# DIY_V2.net
KiCad netlist of a schematic drawn in Altium Designer
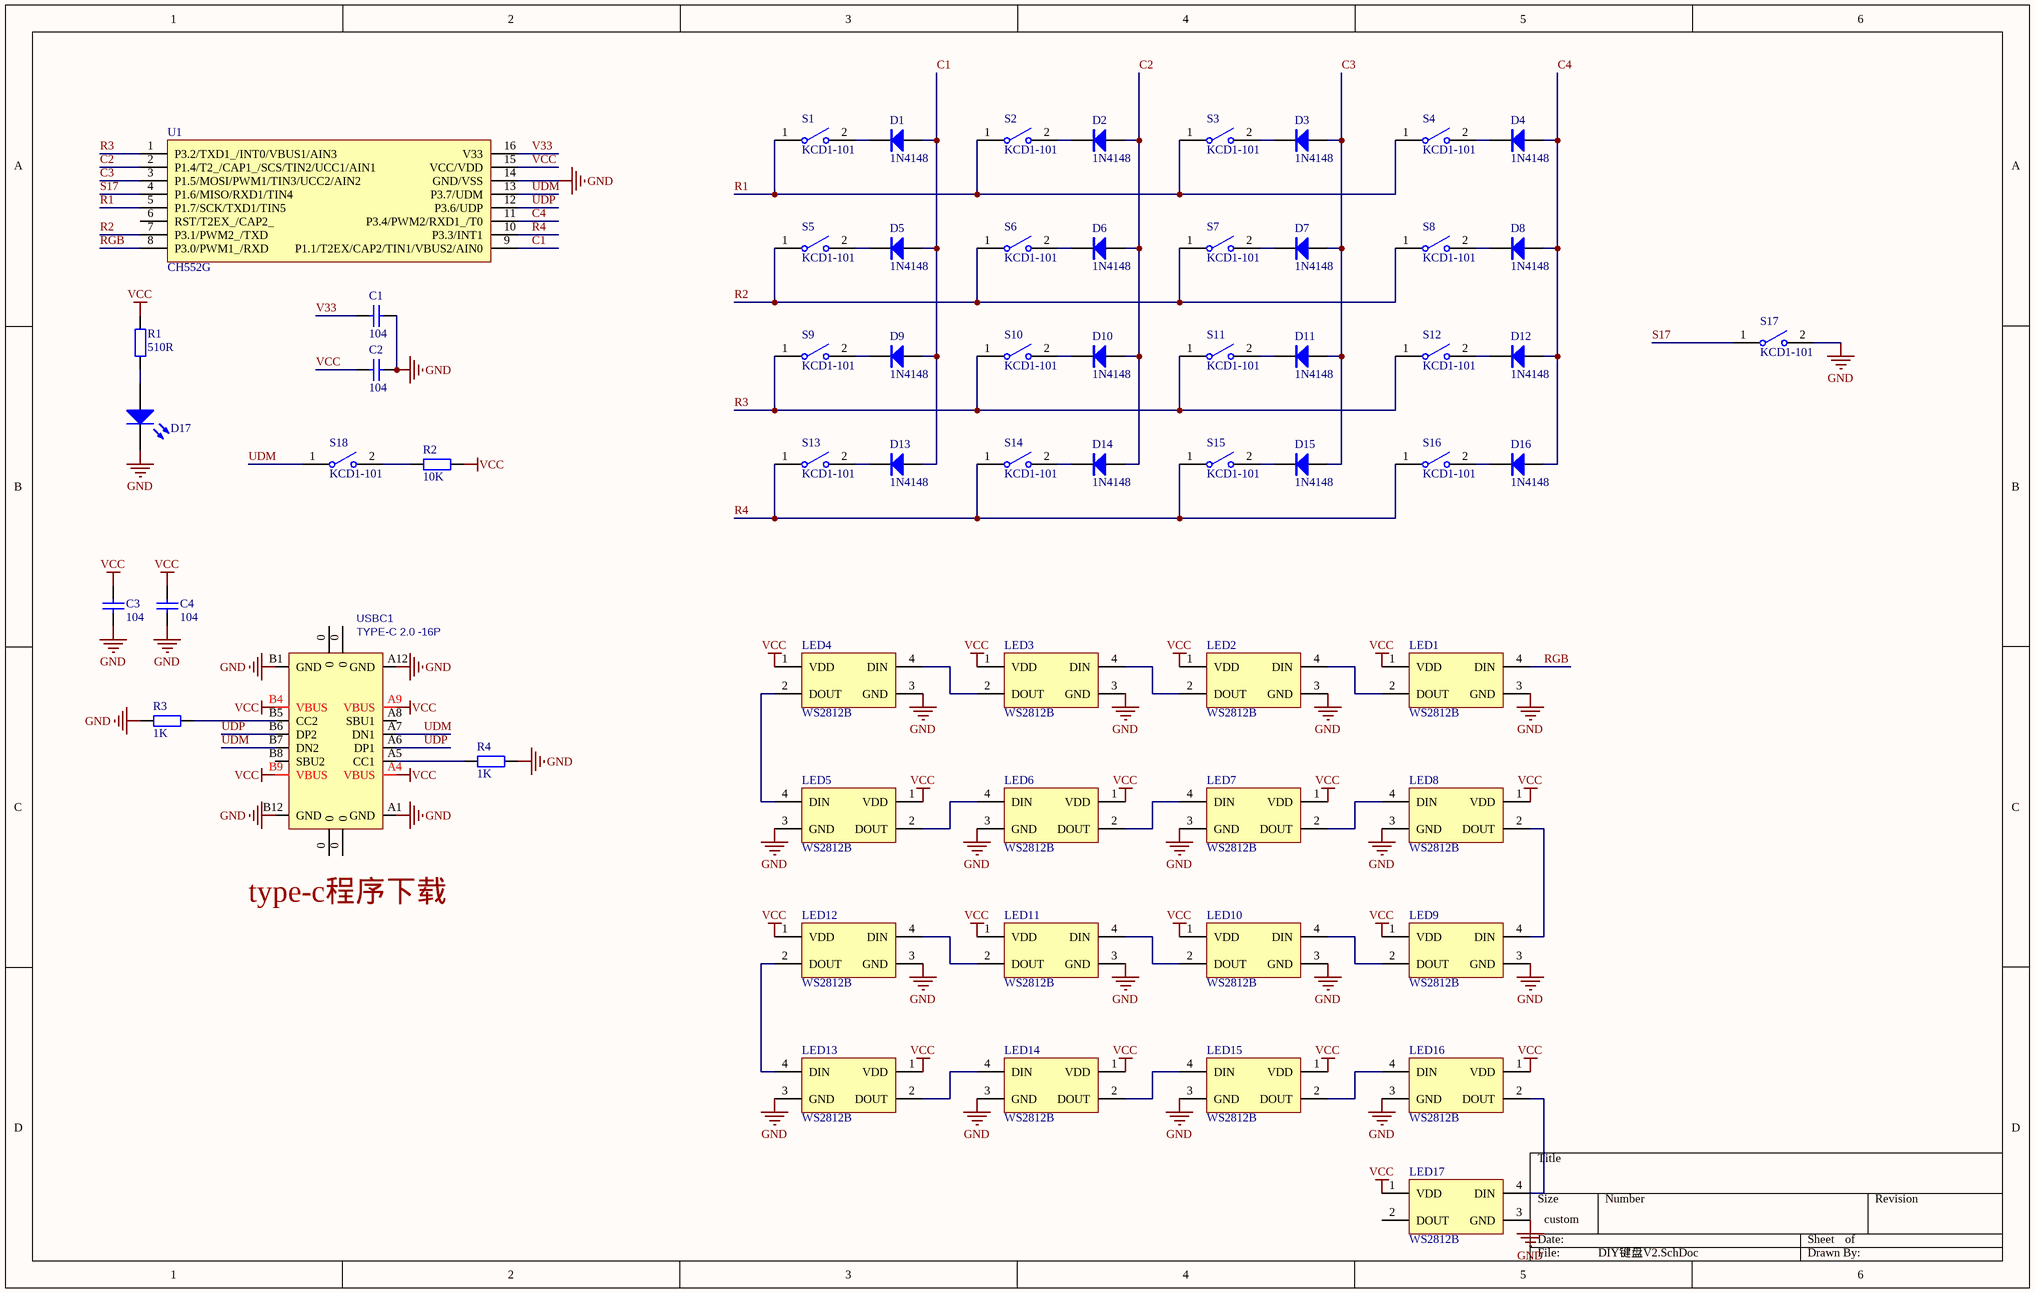
[diagram p0: DIY键盘V2.SchDoc]

(export (version "E")
  (design (tool "Eeschema 10.0.6"))
  (components
    (comp (ref "C1")
      (value "104")
      (footprint "C0603_M")
      (description "贴片电容/MLCC电容")
      (libsource (lib "0.1 - 电阻-电容-电感-晶振-晶体-磁珠-电位器-法拉电容-馈通电容") (part "C"))
    )
    (comp (ref "C2")
      (value "104")
      (footprint "C0603_M")
      (description "贴片电容/MLCC电容")
      (libsource (lib "0.1 - 电阻-电容-电感-晶振-晶体-磁珠-电位器-法拉电容-馈通电容") (part "C"))
    )
    (comp (ref "C3")
      (value "104")
      (footprint "C0603_M")
      (description "贴片电容/MLCC电容")
      (libsource (lib "0.1 - 电阻-电容-电感-晶振-晶体-磁珠-电位器-法拉电容-馈通电容") (part "C"))
    )
    (comp (ref "C4")
      (value "104")
      (footprint "C0603_M")
      (description "贴片电容/MLCC电容")
      (libsource (lib "0.1 - 电阻-电容-电感-晶振-晶体-磁珠-电位器-法拉电容-馈通电容") (part "C"))
    )
    (comp (ref "D1")
      (value "1N4148")
      (footprint "SOD-323")
      (description "开关二极管")
      (libsource (lib "0.2 - 二极管-TVS-ESD-整流桥-放电管") (part "1N4148"))
    )
    (comp (ref "D2")
      (value "1N4148")
      (footprint "SOD-323")
      (description "开关二极管")
      (libsource (lib "0.2 - 二极管-TVS-ESD-整流桥-放电管") (part "1N4148"))
    )
    (comp (ref "D3")
      (value "1N4148")
      (footprint "SOD-323")
      (description "开关二极管")
      (libsource (lib "0.2 - 二极管-TVS-ESD-整流桥-放电管") (part "1N4148"))
    )
    (comp (ref "D4")
      (value "1N4148")
      (footprint "SOD-323")
      (description "开关二极管")
      (libsource (lib "0.2 - 二极管-TVS-ESD-整流桥-放电管") (part "1N4148"))
    )
    (comp (ref "D5")
      (value "1N4148")
      (footprint "SOD-323")
      (description "开关二极管")
      (libsource (lib "0.2 - 二极管-TVS-ESD-整流桥-放电管") (part "1N4148"))
    )
    (comp (ref "D6")
      (value "1N4148")
      (footprint "SOD-323")
      (description "开关二极管")
      (libsource (lib "0.2 - 二极管-TVS-ESD-整流桥-放电管") (part "1N4148"))
    )
    (comp (ref "D7")
      (value "1N4148")
      (footprint "SOD-323")
      (description "开关二极管")
      (libsource (lib "0.2 - 二极管-TVS-ESD-整流桥-放电管") (part "1N4148"))
    )
    (comp (ref "D8")
      (value "1N4148")
      (footprint "SOD-323")
      (description "开关二极管")
      (libsource (lib "0.2 - 二极管-TVS-ESD-整流桥-放电管") (part "1N4148"))
    )
    (comp (ref "D9")
      (value "1N4148")
      (footprint "SOD-323")
      (description "开关二极管")
      (libsource (lib "0.2 - 二极管-TVS-ESD-整流桥-放电管") (part "1N4148"))
    )
    (comp (ref "D10")
      (value "1N4148")
      (footprint "SOD-323")
      (description "开关二极管")
      (libsource (lib "0.2 - 二极管-TVS-ESD-整流桥-放电管") (part "1N4148"))
    )
    (comp (ref "D11")
      (value "1N4148")
      (footprint "SOD-323")
      (description "开关二极管")
      (libsource (lib "0.2 - 二极管-TVS-ESD-整流桥-放电管") (part "1N4148"))
    )
    (comp (ref "D12")
      (value "1N4148")
      (footprint "SOD-323")
      (description "开关二极管")
      (libsource (lib "0.2 - 二极管-TVS-ESD-整流桥-放电管") (part "1N4148"))
    )
    (comp (ref "D13")
      (value "1N4148")
      (footprint "SOD-323")
      (description "开关二极管")
      (libsource (lib "0.2 - 二极管-TVS-ESD-整流桥-放电管") (part "1N4148"))
    )
    (comp (ref "D14")
      (value "1N4148")
      (footprint "SOD-323")
      (description "开关二极管")
      (libsource (lib "0.2 - 二极管-TVS-ESD-整流桥-放电管") (part "1N4148"))
    )
    (comp (ref "D15")
      (value "1N4148")
      (footprint "SOD-323")
      (description "开关二极管")
      (libsource (lib "0.2 - 二极管-TVS-ESD-整流桥-放电管") (part "1N4148"))
    )
    (comp (ref "D16")
      (value "1N4148")
      (footprint "SOD-323")
      (description "开关二极管")
      (libsource (lib "0.2 - 二极管-TVS-ESD-整流桥-放电管") (part "1N4148"))
    )
    (comp (ref "D17")
      (value "LED")
      (footprint "LED0603_B")
      (description "发光二极管")
      (libsource (lib "0.3 - LED发光二极管-IR二极管_接收管-光耦") (part "LED"))
    )
    (comp (ref "LED1")
      (value "WS2812B")
      (footprint "LED-SMD_L3.2-W2.8-BR_DY-S352818")
      (description "WS2812B反贴")
      (libsource (lib "0.3 - LED发光二极管-IR二极管_接收管-光耦") (part "WS2812B"))
    )
    (comp (ref "LED2")
      (value "WS2812B")
      (footprint "LED-SMD_L3.2-W2.8-BR_DY-S352818")
      (description "WS2812B反贴")
      (libsource (lib "0.3 - LED发光二极管-IR二极管_接收管-光耦") (part "WS2812B"))
    )
    (comp (ref "LED3")
      (value "WS2812B")
      (footprint "LED-SMD_L3.2-W2.8-BR_DY-S352818")
      (description "WS2812B反贴")
      (libsource (lib "0.3 - LED发光二极管-IR二极管_接收管-光耦") (part "WS2812B"))
    )
    (comp (ref "LED4")
      (value "WS2812B")
      (footprint "LED-SMD_L3.2-W2.8-BR_DY-S352818")
      (description "WS2812B反贴")
      (libsource (lib "0.3 - LED发光二极管-IR二极管_接收管-光耦") (part "WS2812B"))
    )
    (comp (ref "LED5")
      (value "WS2812B")
      (footprint "LED-SMD_L3.2-W2.8-BR_DY-S352818")
      (description "WS2812B反贴")
      (libsource (lib "") (part "WS2812B_1"))
    )
    (comp (ref "LED6")
      (value "WS2812B")
      (footprint "LED-SMD_L3.2-W2.8-BR_DY-S352818")
      (description "WS2812B反贴")
      (libsource (lib "") (part "WS2812B_1"))
    )
    (comp (ref "LED7")
      (value "WS2812B")
      (footprint "LED-SMD_L3.2-W2.8-BR_DY-S352818")
      (description "WS2812B反贴")
      (libsource (lib "") (part "WS2812B_1"))
    )
    (comp (ref "LED8")
      (value "WS2812B")
      (footprint "LED-SMD_L3.2-W2.8-BR_DY-S352818")
      (description "WS2812B反贴")
      (libsource (lib "") (part "WS2812B_1"))
    )
    (comp (ref "LED9")
      (value "WS2812B")
      (footprint "LED-SMD_L3.2-W2.8-BR_DY-S352818")
      (description "WS2812B反贴")
      (libsource (lib "0.3 - LED发光二极管-IR二极管_接收管-光耦") (part "WS2812B"))
    )
    (comp (ref "LED10")
      (value "WS2812B")
      (footprint "LED-SMD_L3.2-W2.8-BR_DY-S352818")
      (description "WS2812B反贴")
      (libsource (lib "0.3 - LED发光二极管-IR二极管_接收管-光耦") (part "WS2812B"))
    )
    (comp (ref "LED11")
      (value "WS2812B")
      (footprint "LED-SMD_L3.2-W2.8-BR_DY-S352818")
      (description "WS2812B反贴")
      (libsource (lib "0.3 - LED发光二极管-IR二极管_接收管-光耦") (part "WS2812B"))
    )
    (comp (ref "LED12")
      (value "WS2812B")
      (footprint "LED-SMD_L3.2-W2.8-BR_DY-S352818")
      (description "WS2812B反贴")
      (libsource (lib "0.3 - LED发光二极管-IR二极管_接收管-光耦") (part "WS2812B"))
    )
    (comp (ref "LED13")
      (value "WS2812B")
      (footprint "LED-SMD_L3.2-W2.8-BR_DY-S352818")
      (description "WS2812B反贴")
      (libsource (lib "") (part "WS2812B_1"))
    )
    (comp (ref "LED14")
      (value "WS2812B")
      (footprint "LED-SMD_L3.2-W2.8-BR_DY-S352818")
      (description "WS2812B反贴")
      (libsource (lib "") (part "WS2812B_1"))
    )
    (comp (ref "LED15")
      (value "WS2812B")
      (footprint "LED-SMD_L3.2-W2.8-BR_DY-S352818")
      (description "WS2812B反贴")
      (libsource (lib "") (part "WS2812B_1"))
    )
    (comp (ref "LED16")
      (value "WS2812B")
      (footprint "LED-SMD_L3.2-W2.8-BR_DY-S352818")
      (description "WS2812B反贴")
      (libsource (lib "") (part "WS2812B_1"))
    )
    (comp (ref "LED17")
      (value "WS2812B")
      (footprint "LED-SMD_L3.2-W2.8-BR_DY-S352818")
      (description "WS2812B反贴")
      (libsource (lib "0.3 - LED发光二极管-IR二极管_接收管-光耦") (part "WS2812B"))
    )
    (comp (ref "R1")
      (value "510R")
      (footprint "R0603_M")
      (description "贴片电阻")
      (libsource (lib "0.1 - 电阻-电容-电感-晶振-晶体-磁珠-电位器-法拉电容-馈通电容") (part "R"))
    )
    (comp (ref "R2")
      (value "10K")
      (footprint "R0603_M")
      (description "贴片电阻")
      (libsource (lib "0.1 - 电阻-电容-电感-晶振-晶体-磁珠-电位器-法拉电容-馈通电容") (part "R"))
    )
    (comp (ref "R3")
      (value "1K")
      (footprint "R0603_M")
      (description "贴片电阻")
      (libsource (lib "0.1 - 电阻-电容-电感-晶振-晶体-磁珠-电位器-法拉电容-馈通电容") (part "R"))
    )
    (comp (ref "R4")
      (value "1K")
      (footprint "R0603_M")
      (description "贴片电阻")
      (libsource (lib "0.1 - 电阻-电容-电感-晶振-晶体-磁珠-电位器-法拉电容-馈通电容") (part "R"))
    )
    (comp (ref "S1")
      (value "KCD1-101")
      (footprint "DIY键盘:KEY-TH_CPG1511F01S0X")
      (description "1路单刀船型开关")
      (libsource (lib "0.5 - 按键-开关-蜂鸣器-保险丝-电池-测试点-Mark点-铜柱") (part "KCD1-101"))
    )
    (comp (ref "S2")
      (value "KCD1-101")
      (footprint "DIY键盘:KEY-TH_CPG1511F01S0X")
      (description "1路单刀船型开关")
      (libsource (lib "0.5 - 按键-开关-蜂鸣器-保险丝-电池-测试点-Mark点-铜柱") (part "KCD1-101"))
    )
    (comp (ref "S3")
      (value "KCD1-101")
      (footprint "DIY键盘:KEY-TH_CPG1511F01S0X")
      (description "1路单刀船型开关")
      (libsource (lib "0.5 - 按键-开关-蜂鸣器-保险丝-电池-测试点-Mark点-铜柱") (part "KCD1-101"))
    )
    (comp (ref "S4")
      (value "KCD1-101")
      (footprint "DIY键盘:KEY-TH_CPG1511F01S0X")
      (description "1路单刀船型开关")
      (libsource (lib "0.5 - 按键-开关-蜂鸣器-保险丝-电池-测试点-Mark点-铜柱") (part "KCD1-101"))
    )
    (comp (ref "S5")
      (value "KCD1-101")
      (footprint "DIY键盘:KEY-TH_CPG1511F01S0X")
      (description "1路单刀船型开关")
      (libsource (lib "0.5 - 按键-开关-蜂鸣器-保险丝-电池-测试点-Mark点-铜柱") (part "KCD1-101"))
    )
    (comp (ref "S6")
      (value "KCD1-101")
      (footprint "DIY键盘:KEY-TH_CPG1511F01S0X")
      (description "1路单刀船型开关")
      (libsource (lib "0.5 - 按键-开关-蜂鸣器-保险丝-电池-测试点-Mark点-铜柱") (part "KCD1-101"))
    )
    (comp (ref "S7")
      (value "KCD1-101")
      (footprint "DIY键盘:KEY-TH_CPG1511F01S0X")
      (description "1路单刀船型开关")
      (libsource (lib "0.5 - 按键-开关-蜂鸣器-保险丝-电池-测试点-Mark点-铜柱") (part "KCD1-101"))
    )
    (comp (ref "S8")
      (value "KCD1-101")
      (footprint "DIY键盘:KEY-TH_CPG1511F01S0X")
      (description "1路单刀船型开关")
      (libsource (lib "0.5 - 按键-开关-蜂鸣器-保险丝-电池-测试点-Mark点-铜柱") (part "KCD1-101"))
    )
    (comp (ref "S9")
      (value "KCD1-101")
      (footprint "DIY键盘:KEY-TH_CPG1511F01S0X")
      (description "1路单刀船型开关")
      (libsource (lib "0.5 - 按键-开关-蜂鸣器-保险丝-电池-测试点-Mark点-铜柱") (part "KCD1-101"))
    )
    (comp (ref "S10")
      (value "KCD1-101")
      (footprint "DIY键盘:KEY-TH_CPG1511F01S0X")
      (description "1路单刀船型开关")
      (libsource (lib "0.5 - 按键-开关-蜂鸣器-保险丝-电池-测试点-Mark点-铜柱") (part "KCD1-101"))
    )
    (comp (ref "S11")
      (value "KCD1-101")
      (footprint "DIY键盘:KEY-TH_CPG1511F01S0X")
      (description "1路单刀船型开关")
      (libsource (lib "0.5 - 按键-开关-蜂鸣器-保险丝-电池-测试点-Mark点-铜柱") (part "KCD1-101"))
    )
    (comp (ref "S12")
      (value "KCD1-101")
      (footprint "DIY键盘:KEY-TH_CPG1511F01S0X")
      (description "1路单刀船型开关")
      (libsource (lib "0.5 - 按键-开关-蜂鸣器-保险丝-电池-测试点-Mark点-铜柱") (part "KCD1-101"))
    )
    (comp (ref "S13")
      (value "KCD1-101")
      (footprint "DIY键盘:KEY-TH_CPG1511F01S0X")
      (description "1路单刀船型开关")
      (libsource (lib "0.5 - 按键-开关-蜂鸣器-保险丝-电池-测试点-Mark点-铜柱") (part "KCD1-101"))
    )
    (comp (ref "S14")
      (value "KCD1-101")
      (footprint "DIY键盘:KEY-TH_CPG1511F01S0X")
      (description "1路单刀船型开关")
      (libsource (lib "0.5 - 按键-开关-蜂鸣器-保险丝-电池-测试点-Mark点-铜柱") (part "KCD1-101"))
    )
    (comp (ref "S15")
      (value "KCD1-101")
      (footprint "DIY键盘:KEY-TH_CPG1511F01S0X")
      (description "1路单刀船型开关")
      (libsource (lib "0.5 - 按键-开关-蜂鸣器-保险丝-电池-测试点-Mark点-铜柱") (part "KCD1-101"))
    )
    (comp (ref "S16")
      (value "KCD1-101")
      (footprint "DIY键盘:KEY-TH_CPG1511F01S0X")
      (description "1路单刀船型开关")
      (libsource (lib "0.5 - 按键-开关-蜂鸣器-保险丝-电池-测试点-Mark点-铜柱") (part "KCD1-101"))
    )
    (comp (ref "S17")
      (value "KCD1-101")
      (footprint "DIY键盘:KEY-TH_CPG1511F01S0X")
      (description "1路单刀船型开关")
      (libsource (lib "0.5 - 按键-开关-蜂鸣器-保险丝-电池-测试点-Mark点-铜柱") (part "KCD1-101"))
    )
    (comp (ref "S18")
      (value "KCD1-101")
      (footprint "SW SMD-3*6*2.5")
      (description "1路单刀船型开关")
      (libsource (lib "0.5 - 按键-开关-蜂鸣器-保险丝-电池-测试点-Mark点-铜柱") (part "KCD1-101"))
    )
    (comp (ref "U1")
      (value "CH552G")
      (footprint "DIY键盘:SOP-16_L10.0-W3.9-P1.27-LS6.0-BL")
      (description "8 DIgits")
      (libsource (lib "1.8 - CH340系列编程器芯片") (part "CH552G"))
    )
    (comp (ref "USBC1")
      (value "TYPE-C 2.0 -16P")
      (footprint "USB-C-SMD_16P")
      (description "USB2.0_Type-C_16Pin母座")
      (libsource (lib "0.6 - 电源-以太网-音频-Type-C USB插座") (part "USB2.0_Type-C_16Pin"))
    )
  )
  (nets
    (net (code "1") (name "/C1") (class "Default")
      (node (ref "D1") (pin "1") (pinfunction "A_1") (pintype "passive"))
      (node (ref "D13") (pin "1") (pinfunction "A_1") (pintype "passive"))
      (node (ref "D5") (pin "1") (pinfunction "A_1") (pintype "passive"))
      (node (ref "D9") (pin "1") (pinfunction "A_1") (pintype "passive"))
      (node (ref "U1") (pin "9") (pinfunction "P1.1/T2EX/CAP2/TIN1/VBUS2/AIN0_9") (pintype "passive"))
    )
    (net (code "2") (name "/C2") (class "Default")
      (node (ref "D10") (pin "1") (pinfunction "A_1") (pintype "passive"))
      (node (ref "D14") (pin "1") (pinfunction "A_1") (pintype "passive"))
      (node (ref "D2") (pin "1") (pinfunction "A_1") (pintype "passive"))
      (node (ref "D6") (pin "1") (pinfunction "A_1") (pintype "passive"))
      (node (ref "U1") (pin "2") (pinfunction "P1.4/T2_/CAP1_/SCS/TIN2/UCC1/AIN1_2") (pintype "passive"))
    )
    (net (code "3") (name "/C3") (class "Default")
      (node (ref "D11") (pin "1") (pinfunction "A_1") (pintype "passive"))
      (node (ref "D15") (pin "1") (pinfunction "A_1") (pintype "passive"))
      (node (ref "D3") (pin "1") (pinfunction "A_1") (pintype "passive"))
      (node (ref "D7") (pin "1") (pinfunction "A_1") (pintype "passive"))
      (node (ref "U1") (pin "3") (pinfunction "P1.5/MOSI/PWM1/TIN3/UCC2/AIN2_3") (pintype "passive"))
    )
    (net (code "4") (name "/C4") (class "Default")
      (node (ref "D12") (pin "1") (pinfunction "A_1") (pintype "passive"))
      (node (ref "D16") (pin "1") (pinfunction "A_1") (pintype "passive"))
      (node (ref "D4") (pin "1") (pinfunction "A_1") (pintype "passive"))
      (node (ref "D8") (pin "1") (pinfunction "A_1") (pintype "passive"))
      (node (ref "U1") (pin "11") (pinfunction "P3.4/PWM2/RXD1_/T0_11") (pintype "passive"))
    )
    (net (code "5") (name "/R1") (class "Default")
      (node (ref "S1") (pin "1") (pinfunction "1_1") (pintype "passive"))
      (node (ref "S2") (pin "1") (pinfunction "1_1") (pintype "passive"))
      (node (ref "S3") (pin "1") (pinfunction "1_1") (pintype "passive"))
      (node (ref "S4") (pin "1") (pinfunction "1_1") (pintype "passive"))
      (node (ref "U1") (pin "5") (pinfunction "P1.7/SCK/TXD1/TIN5_5") (pintype "passive"))
    )
    (net (code "6") (name "/R2") (class "Default")
      (node (ref "S5") (pin "1") (pinfunction "1_1") (pintype "passive"))
      (node (ref "S6") (pin "1") (pinfunction "1_1") (pintype "passive"))
      (node (ref "S7") (pin "1") (pinfunction "1_1") (pintype "passive"))
      (node (ref "S8") (pin "1") (pinfunction "1_1") (pintype "passive"))
      (node (ref "U1") (pin "7") (pinfunction "P3.1/PWM2_/TXD_7") (pintype "passive"))
    )
    (net (code "7") (name "/R3") (class "Default")
      (node (ref "S10") (pin "1") (pinfunction "1_1") (pintype "passive"))
      (node (ref "S11") (pin "1") (pinfunction "1_1") (pintype "passive"))
      (node (ref "S12") (pin "1") (pinfunction "1_1") (pintype "passive"))
      (node (ref "S9") (pin "1") (pinfunction "1_1") (pintype "passive"))
      (node (ref "U1") (pin "1") (pinfunction "P3.2/TXD1_/INT0/VBUS1/AIN3_1") (pintype "passive"))
    )
    (net (code "8") (name "/R4") (class "Default")
      (node (ref "S13") (pin "1") (pinfunction "1_1") (pintype "passive"))
      (node (ref "S14") (pin "1") (pinfunction "1_1") (pintype "passive"))
      (node (ref "S15") (pin "1") (pinfunction "1_1") (pintype "passive"))
      (node (ref "S16") (pin "1") (pinfunction "1_1") (pintype "passive"))
      (node (ref "U1") (pin "10") (pinfunction "P3.3/INT1_10") (pintype "passive"))
    )
    (net (code "9") (name "/RGB") (class "Default")
      (node (ref "LED1") (pin "4") (pinfunction "DIN_4") (pintype "passive"))
      (node (ref "U1") (pin "8") (pinfunction "P3.0/PWM1_/RXD_8") (pintype "passive"))
    )
    (net (code "10") (name "/S17") (class "Default")
      (node (ref "S17") (pin "1") (pinfunction "1_1") (pintype "passive"))
      (node (ref "U1") (pin "4") (pinfunction "P1.6/MISO/RXD1/TIN4_4") (pintype "passive"))
    )
    (net (code "11") (name "/UDM") (class "Default")
      (node (ref "S18") (pin "1") (pinfunction "1_1") (pintype "passive"))
      (node (ref "U1") (pin "13") (pinfunction "P3.7/UDM_13") (pintype "passive"))
      (node (ref "USBC1") (pin "A7") (pinfunction "DN1_A7") (pintype "passive"))
      (node (ref "USBC1") (pin "B7") (pinfunction "DN2_B7") (pintype "passive"))
    )
    (net (code "12") (name "/UDP") (class "Default")
      (node (ref "U1") (pin "12") (pinfunction "P3.6/UDP_12") (pintype "passive"))
      (node (ref "USBC1") (pin "A6") (pinfunction "DP1_A6") (pintype "passive"))
      (node (ref "USBC1") (pin "B6") (pinfunction "DP2_B6") (pintype "passive"))
    )
    (net (code "13") (name "/V33") (class "Default")
      (node (ref "C1") (pin "2") (pinfunction "2_2") (pintype "passive"))
      (node (ref "U1") (pin "16") (pinfunction "V33_16") (pintype "passive"))
    )
    (net (code "14") (name "GND") (class "Default")
      (node (ref "C1") (pin "1") (pinfunction "1_1") (pintype "passive"))
      (node (ref "C2") (pin "1") (pinfunction "1_1") (pintype "passive"))
      (node (ref "C3") (pin "1") (pinfunction "1_1") (pintype "passive"))
      (node (ref "C4") (pin "1") (pinfunction "1_1") (pintype "passive"))
      (node (ref "D17") (pin "2") (pinfunction "K_2") (pintype "passive"))
      (node (ref "LED1") (pin "3") (pinfunction "GND_3") (pintype "passive"))
      (node (ref "LED10") (pin "3") (pinfunction "GND_3") (pintype "passive"))
      (node (ref "LED11") (pin "3") (pinfunction "GND_3") (pintype "passive"))
      (node (ref "LED12") (pin "3") (pinfunction "GND_3") (pintype "passive"))
      (node (ref "LED13") (pin "3") (pinfunction "GND_3") (pintype "passive"))
      (node (ref "LED14") (pin "3") (pinfunction "GND_3") (pintype "passive"))
      (node (ref "LED15") (pin "3") (pinfunction "GND_3") (pintype "passive"))
      (node (ref "LED16") (pin "3") (pinfunction "GND_3") (pintype "passive"))
      (node (ref "LED17") (pin "3") (pinfunction "GND_3") (pintype "passive"))
      (node (ref "LED2") (pin "3") (pinfunction "GND_3") (pintype "passive"))
      (node (ref "LED3") (pin "3") (pinfunction "GND_3") (pintype "passive"))
      (node (ref "LED4") (pin "3") (pinfunction "GND_3") (pintype "passive"))
      (node (ref "LED5") (pin "3") (pinfunction "GND_3") (pintype "passive"))
      (node (ref "LED6") (pin "3") (pinfunction "GND_3") (pintype "passive"))
      (node (ref "LED7") (pin "3") (pinfunction "GND_3") (pintype "passive"))
      (node (ref "LED8") (pin "3") (pinfunction "GND_3") (pintype "passive"))
      (node (ref "LED9") (pin "3") (pinfunction "GND_3") (pintype "passive"))
      (node (ref "R3") (pin "2") (pinfunction "2_2") (pintype "passive"))
      (node (ref "R4") (pin "2") (pinfunction "2_2") (pintype "passive"))
      (node (ref "S17") (pin "2") (pinfunction "2_2") (pintype "passive"))
      (node (ref "U1") (pin "14") (pinfunction "GND/VSS_14") (pintype "passive"))
      (node (ref "USBC1") (pin "A1") (pinfunction "GND_A1") (pintype "passive"))
      (node (ref "USBC1") (pin "A12") (pinfunction "GND_A12") (pintype "passive"))
      (node (ref "USBC1") (pin "B1") (pinfunction "GND_B1") (pintype "passive"))
      (node (ref "USBC1") (pin "B12") (pinfunction "GND_B12") (pintype "passive"))
    )
    (net (code "15") (name "Net-(D1-K)") (class "Default")
      (node (ref "D1") (pin "2") (pinfunction "K_2") (pintype "passive"))
      (node (ref "S1") (pin "2") (pinfunction "2_2") (pintype "passive"))
    )
    (net (code "16") (name "Net-(D2-K)") (class "Default")
      (node (ref "D2") (pin "2") (pinfunction "K_2") (pintype "passive"))
      (node (ref "S2") (pin "2") (pinfunction "2_2") (pintype "passive"))
    )
    (net (code "17") (name "Net-(D3-K)") (class "Default")
      (node (ref "D3") (pin "2") (pinfunction "K_2") (pintype "passive"))
      (node (ref "S3") (pin "2") (pinfunction "2_2") (pintype "passive"))
    )
    (net (code "18") (name "Net-(D4-K)") (class "Default")
      (node (ref "D4") (pin "2") (pinfunction "K_2") (pintype "passive"))
      (node (ref "S4") (pin "2") (pinfunction "2_2") (pintype "passive"))
    )
    (net (code "19") (name "Net-(D5-K)") (class "Default")
      (node (ref "D5") (pin "2") (pinfunction "K_2") (pintype "passive"))
      (node (ref "S5") (pin "2") (pinfunction "2_2") (pintype "passive"))
    )
    (net (code "20") (name "Net-(D6-K)") (class "Default")
      (node (ref "D6") (pin "2") (pinfunction "K_2") (pintype "passive"))
      (node (ref "S6") (pin "2") (pinfunction "2_2") (pintype "passive"))
    )
    (net (code "21") (name "Net-(D7-K)") (class "Default")
      (node (ref "D7") (pin "2") (pinfunction "K_2") (pintype "passive"))
      (node (ref "S7") (pin "2") (pinfunction "2_2") (pintype "passive"))
    )
    (net (code "22") (name "Net-(D8-K)") (class "Default")
      (node (ref "D8") (pin "2") (pinfunction "K_2") (pintype "passive"))
      (node (ref "S8") (pin "2") (pinfunction "2_2") (pintype "passive"))
    )
    (net (code "23") (name "Net-(D9-K)") (class "Default")
      (node (ref "D9") (pin "2") (pinfunction "K_2") (pintype "passive"))
      (node (ref "S9") (pin "2") (pinfunction "2_2") (pintype "passive"))
    )
    (net (code "24") (name "Net-(D10-K)") (class "Default")
      (node (ref "D10") (pin "2") (pinfunction "K_2") (pintype "passive"))
      (node (ref "S10") (pin "2") (pinfunction "2_2") (pintype "passive"))
    )
    (net (code "25") (name "Net-(D11-K)") (class "Default")
      (node (ref "D11") (pin "2") (pinfunction "K_2") (pintype "passive"))
      (node (ref "S11") (pin "2") (pinfunction "2_2") (pintype "passive"))
    )
    (net (code "26") (name "Net-(D12-K)") (class "Default")
      (node (ref "D12") (pin "2") (pinfunction "K_2") (pintype "passive"))
      (node (ref "S12") (pin "2") (pinfunction "2_2") (pintype "passive"))
    )
    (net (code "27") (name "Net-(D13-K)") (class "Default")
      (node (ref "D13") (pin "2") (pinfunction "K_2") (pintype "passive"))
      (node (ref "S13") (pin "2") (pinfunction "2_2") (pintype "passive"))
    )
    (net (code "28") (name "Net-(D14-K)") (class "Default")
      (node (ref "D14") (pin "2") (pinfunction "K_2") (pintype "passive"))
      (node (ref "S14") (pin "2") (pinfunction "2_2") (pintype "passive"))
    )
    (net (code "29") (name "Net-(D15-K)") (class "Default")
      (node (ref "D15") (pin "2") (pinfunction "K_2") (pintype "passive"))
      (node (ref "S15") (pin "2") (pinfunction "2_2") (pintype "passive"))
    )
    (net (code "30") (name "Net-(D16-K)") (class "Default")
      (node (ref "D16") (pin "2") (pinfunction "K_2") (pintype "passive"))
      (node (ref "S16") (pin "2") (pinfunction "2_2") (pintype "passive"))
    )
    (net (code "31") (name "Net-(D17-A)") (class "Default")
      (node (ref "D17") (pin "1") (pinfunction "A_1") (pintype "passive"))
      (node (ref "R1") (pin "1") (pinfunction "1_1") (pintype "passive"))
    )
    (net (code "32") (name "Net-(LED1-DOUT)") (class "Default")
      (node (ref "LED1") (pin "2") (pinfunction "DOUT_2") (pintype "passive"))
      (node (ref "LED2") (pin "4") (pinfunction "DIN_4") (pintype "passive"))
    )
    (net (code "33") (name "Net-(LED2-DOUT)") (class "Default")
      (node (ref "LED2") (pin "2") (pinfunction "DOUT_2") (pintype "passive"))
      (node (ref "LED3") (pin "4") (pinfunction "DIN_4") (pintype "passive"))
    )
    (net (code "34") (name "Net-(LED3-DOUT)") (class "Default")
      (node (ref "LED3") (pin "2") (pinfunction "DOUT_2") (pintype "passive"))
      (node (ref "LED4") (pin "4") (pinfunction "DIN_4") (pintype "passive"))
    )
    (net (code "35") (name "Net-(LED4-DOUT)") (class "Default")
      (node (ref "LED4") (pin "2") (pinfunction "DOUT_2") (pintype "passive"))
      (node (ref "LED5") (pin "4") (pinfunction "DIN_4") (pintype "passive"))
    )
    (net (code "36") (name "Net-(LED5-DOUT)") (class "Default")
      (node (ref "LED5") (pin "2") (pinfunction "DOUT_2") (pintype "passive"))
      (node (ref "LED6") (pin "4") (pinfunction "DIN_4") (pintype "passive"))
    )
    (net (code "37") (name "Net-(LED6-DOUT)") (class "Default")
      (node (ref "LED6") (pin "2") (pinfunction "DOUT_2") (pintype "passive"))
      (node (ref "LED7") (pin "4") (pinfunction "DIN_4") (pintype "passive"))
    )
    (net (code "38") (name "Net-(LED7-DOUT)") (class "Default")
      (node (ref "LED7") (pin "2") (pinfunction "DOUT_2") (pintype "passive"))
      (node (ref "LED8") (pin "4") (pinfunction "DIN_4") (pintype "passive"))
    )
    (net (code "39") (name "Net-(LED8-DOUT)") (class "Default")
      (node (ref "LED8") (pin "2") (pinfunction "DOUT_2") (pintype "passive"))
      (node (ref "LED9") (pin "4") (pinfunction "DIN_4") (pintype "passive"))
    )
    (net (code "40") (name "Net-(LED10-DIN)") (class "Default")
      (node (ref "LED10") (pin "4") (pinfunction "DIN_4") (pintype "passive"))
      (node (ref "LED9") (pin "2") (pinfunction "DOUT_2") (pintype "passive"))
    )
    (net (code "41") (name "Net-(LED10-DOUT)") (class "Default")
      (node (ref "LED10") (pin "2") (pinfunction "DOUT_2") (pintype "passive"))
      (node (ref "LED11") (pin "4") (pinfunction "DIN_4") (pintype "passive"))
    )
    (net (code "42") (name "Net-(LED11-DOUT)") (class "Default")
      (node (ref "LED11") (pin "2") (pinfunction "DOUT_2") (pintype "passive"))
      (node (ref "LED12") (pin "4") (pinfunction "DIN_4") (pintype "passive"))
    )
    (net (code "43") (name "Net-(LED12-DOUT)") (class "Default")
      (node (ref "LED12") (pin "2") (pinfunction "DOUT_2") (pintype "passive"))
      (node (ref "LED13") (pin "4") (pinfunction "DIN_4") (pintype "passive"))
    )
    (net (code "44") (name "Net-(LED13-DOUT)") (class "Default")
      (node (ref "LED13") (pin "2") (pinfunction "DOUT_2") (pintype "passive"))
      (node (ref "LED14") (pin "4") (pinfunction "DIN_4") (pintype "passive"))
    )
    (net (code "45") (name "Net-(LED14-DOUT)") (class "Default")
      (node (ref "LED14") (pin "2") (pinfunction "DOUT_2") (pintype "passive"))
      (node (ref "LED15") (pin "4") (pinfunction "DIN_4") (pintype "passive"))
    )
    (net (code "46") (name "Net-(LED15-DOUT)") (class "Default")
      (node (ref "LED15") (pin "2") (pinfunction "DOUT_2") (pintype "passive"))
      (node (ref "LED16") (pin "4") (pinfunction "DIN_4") (pintype "passive"))
    )
    (net (code "47") (name "Net-(LED16-DOUT)") (class "Default")
      (node (ref "LED16") (pin "2") (pinfunction "DOUT_2") (pintype "passive"))
      (node (ref "LED17") (pin "4") (pinfunction "DIN_4") (pintype "passive"))
    )
    (net (code "48") (name "Net-(R2-Pad1)") (class "Default")
      (node (ref "R2") (pin "1") (pinfunction "1_1") (pintype "passive"))
      (node (ref "S18") (pin "2") (pinfunction "2_2") (pintype "passive"))
    )
    (net (code "49") (name "Net-(USBC1-CC1)") (class "Default")
      (node (ref "R4") (pin "1") (pinfunction "1_1") (pintype "passive"))
      (node (ref "USBC1") (pin "A5") (pinfunction "CC1_A5") (pintype "passive"))
    )
    (net (code "50") (name "Net-(USBC1-CC2)") (class "Default")
      (node (ref "R3") (pin "1") (pinfunction "1_1") (pintype "passive"))
      (node (ref "USBC1") (pin "B5") (pinfunction "CC2_B5") (pintype "passive"))
    )
    (net (code "51") (name "VCC") (class "Default")
      (node (ref "C2") (pin "2") (pinfunction "2_2") (pintype "passive"))
      (node (ref "C3") (pin "2") (pinfunction "2_2") (pintype "passive"))
      (node (ref "C4") (pin "2") (pinfunction "2_2") (pintype "passive"))
      (node (ref "LED1") (pin "1") (pinfunction "VDD_1") (pintype "passive"))
      (node (ref "LED10") (pin "1") (pinfunction "VDD_1") (pintype "passive"))
      (node (ref "LED11") (pin "1") (pinfunction "VDD_1") (pintype "passive"))
      (node (ref "LED12") (pin "1") (pinfunction "VDD_1") (pintype "passive"))
      (node (ref "LED13") (pin "1") (pinfunction "VDD_1") (pintype "passive"))
      (node (ref "LED14") (pin "1") (pinfunction "VDD_1") (pintype "passive"))
      (node (ref "LED15") (pin "1") (pinfunction "VDD_1") (pintype "passive"))
      (node (ref "LED16") (pin "1") (pinfunction "VDD_1") (pintype "passive"))
      (node (ref "LED17") (pin "1") (pinfunction "VDD_1") (pintype "passive"))
      (node (ref "LED2") (pin "1") (pinfunction "VDD_1") (pintype "passive"))
      (node (ref "LED3") (pin "1") (pinfunction "VDD_1") (pintype "passive"))
      (node (ref "LED4") (pin "1") (pinfunction "VDD_1") (pintype "passive"))
      (node (ref "LED5") (pin "1") (pinfunction "VDD_1") (pintype "passive"))
      (node (ref "LED6") (pin "1") (pinfunction "VDD_1") (pintype "passive"))
      (node (ref "LED7") (pin "1") (pinfunction "VDD_1") (pintype "passive"))
      (node (ref "LED8") (pin "1") (pinfunction "VDD_1") (pintype "passive"))
      (node (ref "LED9") (pin "1") (pinfunction "VDD_1") (pintype "passive"))
      (node (ref "R1") (pin "2") (pinfunction "2_2") (pintype "passive"))
      (node (ref "R2") (pin "2") (pinfunction "2_2") (pintype "passive"))
      (node (ref "U1") (pin "15") (pinfunction "VCC/VDD_15") (pintype "passive"))
      (node (ref "USBC1") (pin "A4") (pinfunction "VBUS_A4") (pintype "passive"))
      (node (ref "USBC1") (pin "A9") (pinfunction "VBUS_A9") (pintype "passive"))
      (node (ref "USBC1") (pin "B4") (pinfunction "VBUS_B4") (pintype "passive"))
      (node (ref "USBC1") (pin "B9") (pinfunction "VBUS_B9") (pintype "passive"))
    )
    (net (code "52") (name "unconnected-(LED17-DOUT-Pad2)") (class "Default")
      (node (ref "LED17") (pin "2") (pinfunction "DOUT_2") (pintype "passive"))
    )
    (net (code "53") (name "unconnected-(U1-RST{slash}T2EX_{slash}CAP2_-Pad6)") (class "Default")
      (node (ref "U1") (pin "6") (pinfunction "RST/T2EX_/CAP2__6") (pintype "passive"))
    )
    (net (code "54") (name "unconnected-(USBC1-Pad0)") (class "Default")
      (node (ref "USBC1") (pin "0") (pinfunction "0_0") (pintype "passive"))
    )
    (net (code "55") (name "unconnected-(USBC1-Pad0)_1") (class "Default")
      (node (ref "USBC1") (pin "0") (pinfunction "0_0") (pintype "passive"))
    )
    (net (code "56") (name "unconnected-(USBC1-Pad0)_2") (class "Default")
      (node (ref "USBC1") (pin "0") (pinfunction "0_0") (pintype "passive"))
    )
    (net (code "57") (name "unconnected-(USBC1-Pad0)_3") (class "Default")
      (node (ref "USBC1") (pin "0") (pinfunction "0_0") (pintype "passive"))
    )
    (net (code "58") (name "unconnected-(USBC1-SBU1-PadA8)") (class "Default")
      (node (ref "USBC1") (pin "A8") (pinfunction "SBU1_A8") (pintype "passive"))
    )
    (net (code "59") (name "unconnected-(USBC1-SBU2-PadB8)") (class "Default")
      (node (ref "USBC1") (pin "B8") (pinfunction "SBU2_B8") (pintype "passive"))
    )
  )
)
